# XMOS_TSBOARD_DAC.net
KiCad netlist of a schematic drawn in Altium Designer
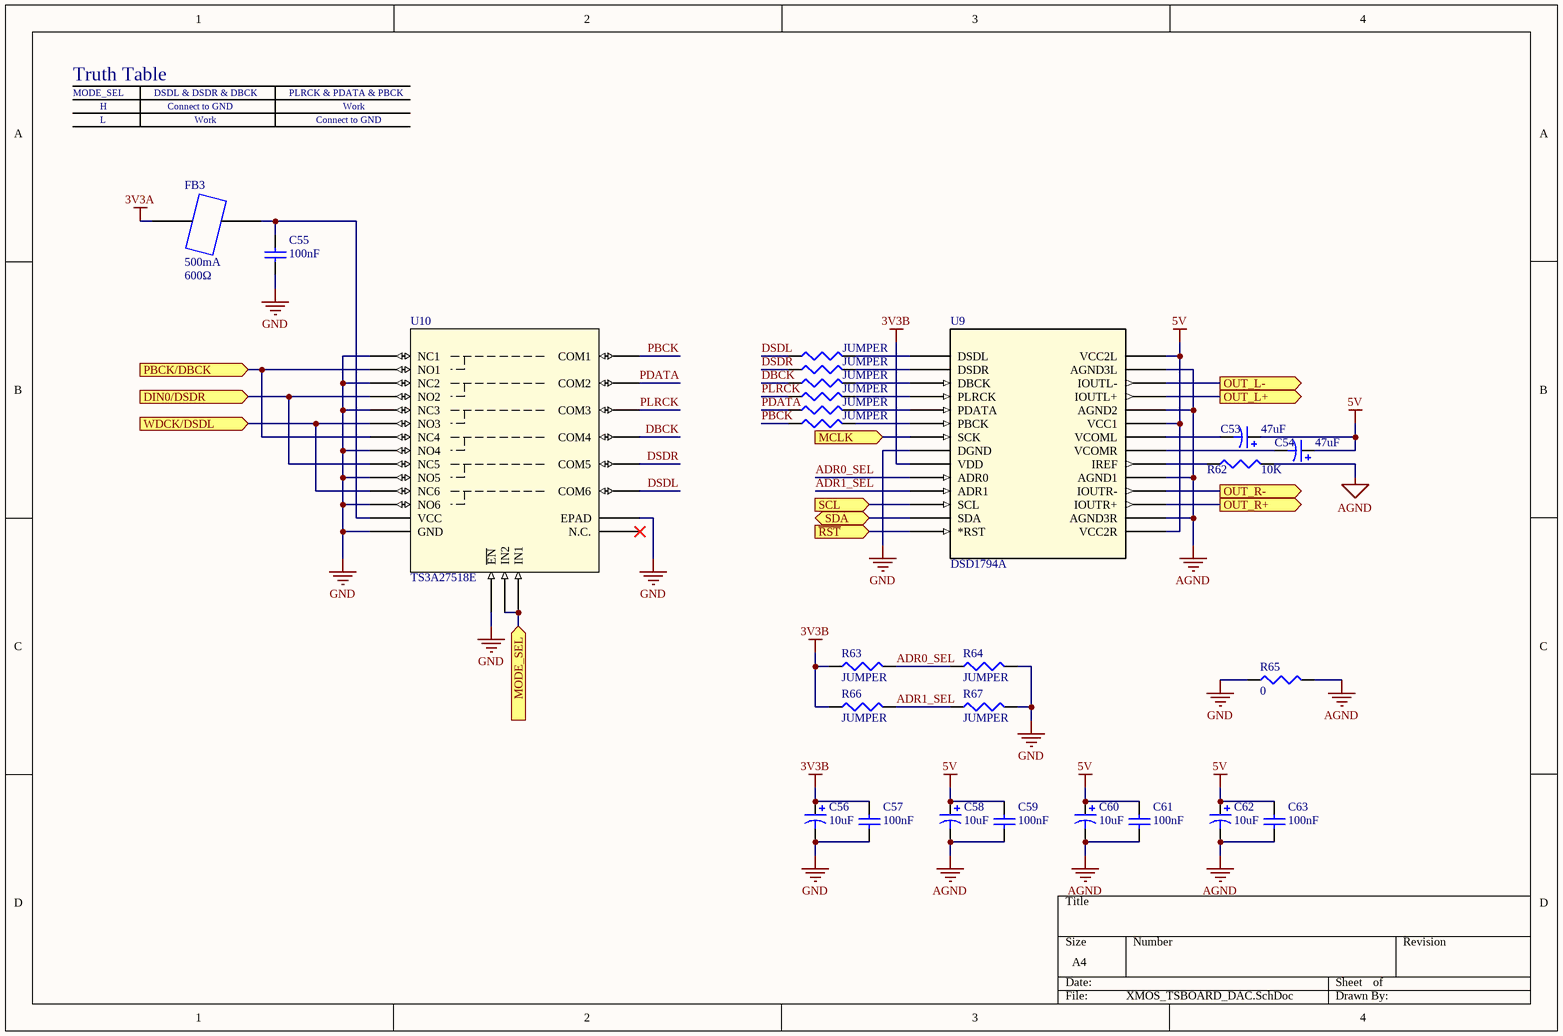
[diagram p0: XMOS_TSBOARD_DAC.SchDoc]

(export (version "E")
  (design (tool "Eeschema 10.0.6"))
  (components
    (comp (ref "C53")
      (value "47uF")
      (footprint "C0805")
      (description "Polarized Capacitor (Surface Mount)")
      (fields (field (name "Comment") "Cap Pol3") (field (name "PUBLISHER") "Altium Limited"))
      (libsource (lib "Miscellaneous Devices") (part "Cap Pol3"))
    )
    (comp (ref "C54")
      (value "47uF")
      (footprint "C0805")
      (description "Polarized Capacitor (Surface Mount)")
      (fields (field (name "Comment") "Cap Pol3") (field (name "PUBLISHER") "Altium Limited"))
      (libsource (lib "Miscellaneous Devices") (part "Cap Pol3"))
    )
    (comp (ref "C55")
      (value "100nF")
      (footprint "1608[0603]")
      (description "Capacitor (Semiconductor SIM Model)")
      (fields (field (name "Comment") "Cap Semi") (field (name "PUBLISHER") "Altium Limited"))
      (libsource (lib "Miscellaneous Devices") (part "Cap Semi"))
    )
    (comp (ref "C56")
      (value "10uF")
      (footprint "C0805")
      (description "Polarized Capacitor (Surface Mount)")
      (fields (field (name "Comment") "Cap Pol3") (field (name "PUBLISHER") "Altium Limited"))
      (libsource (lib "Miscellaneous Devices") (part "Cap Pol3"))
    )
    (comp (ref "C57")
      (value "100nF")
      (footprint "1608[0603]")
      (description "Capacitor (Semiconductor SIM Model)")
      (fields (field (name "Comment") "Cap Semi") (field (name "PUBLISHER") "Altium Limited"))
      (libsource (lib "Miscellaneous Devices") (part "Cap Semi"))
    )
    (comp (ref "C58")
      (value "10uF")
      (footprint "C0805")
      (description "Polarized Capacitor (Surface Mount)")
      (fields (field (name "Comment") "Cap Pol3") (field (name "PUBLISHER") "Altium Limited"))
      (libsource (lib "Miscellaneous Devices") (part "Cap Pol3"))
    )
    (comp (ref "C59")
      (value "100nF")
      (footprint "1608[0603]")
      (description "Capacitor (Semiconductor SIM Model)")
      (fields (field (name "Comment") "Cap Semi") (field (name "PUBLISHER") "Altium Limited"))
      (libsource (lib "Miscellaneous Devices") (part "Cap Semi"))
    )
    (comp (ref "C60")
      (value "10uF")
      (footprint "C0805")
      (description "Polarized Capacitor (Surface Mount)")
      (fields (field (name "Comment") "Cap Pol3") (field (name "PUBLISHER") "Altium Limited"))
      (libsource (lib "Miscellaneous Devices") (part "Cap Pol3"))
    )
    (comp (ref "C61")
      (value "100nF")
      (footprint "1608[0603]")
      (description "Capacitor (Semiconductor SIM Model)")
      (fields (field (name "Comment") "Cap Semi") (field (name "PUBLISHER") "Altium Limited"))
      (libsource (lib "Miscellaneous Devices") (part "Cap Semi"))
    )
    (comp (ref "C62")
      (value "10uF")
      (footprint "C0805")
      (description "Polarized Capacitor (Surface Mount)")
      (fields (field (name "Comment") "Cap Pol3") (field (name "PUBLISHER") "Altium Limited"))
      (libsource (lib "Miscellaneous Devices") (part "Cap Pol3"))
    )
    (comp (ref "C63")
      (value "100nF")
      (footprint "1608[0603]")
      (description "Capacitor (Semiconductor SIM Model)")
      (fields (field (name "Comment") "Cap Semi") (field (name "PUBLISHER") "Altium Limited"))
      (libsource (lib "Miscellaneous Devices") (part "Cap Semi"))
    )
    (comp (ref "FB3")
      (value "FerriteBeads")
      (footprint "0603")
      (description "Chip Ferrite Beads")
      (fields (field (name "RATEDCURRENT") "500mA") (field (name "IMPEDANCE(100MHZ)") "600Ω"))
      (libsource (lib "Troposphere_lib") (part "FerriteBeads"))
    )
    (comp (ref "R56")
      (value "JUMPER")
      (footprint "J1-0603")
      (description "Resistor")
      (fields (field (name "PUBLISHER") "Altium Limited"))
      (libsource (lib "Miscellaneous Devices") (part "Res3"))
    )
    (comp (ref "R57")
      (value "JUMPER")
      (footprint "J1-0603")
      (description "Resistor")
      (fields (field (name "PUBLISHER") "Altium Limited"))
      (libsource (lib "Miscellaneous Devices") (part "Res3"))
    )
    (comp (ref "R58")
      (value "JUMPER")
      (footprint "J1-0603")
      (description "Resistor")
      (fields (field (name "PUBLISHER") "Altium Limited"))
      (libsource (lib "Miscellaneous Devices") (part "Res3"))
    )
    (comp (ref "R59")
      (value "JUMPER")
      (footprint "J1-0603")
      (description "Resistor")
      (fields (field (name "PUBLISHER") "Altium Limited"))
      (libsource (lib "Miscellaneous Devices") (part "Res3"))
    )
    (comp (ref "R60")
      (value "JUMPER")
      (footprint "J1-0603")
      (description "Resistor")
      (fields (field (name "PUBLISHER") "Altium Limited"))
      (libsource (lib "Miscellaneous Devices") (part "Res3"))
    )
    (comp (ref "R61")
      (value "JUMPER")
      (footprint "J1-0603")
      (description "Resistor")
      (fields (field (name "PUBLISHER") "Altium Limited"))
      (libsource (lib "Miscellaneous Devices") (part "Res3"))
    )
    (comp (ref "R62")
      (value "10K")
      (footprint "J1-0603")
      (description "Resistor")
      (fields (field (name "Comment") "Res3") (field (name "PUBLISHER") "Altium Limited"))
      (libsource (lib "Miscellaneous Devices") (part "Res3"))
    )
    (comp (ref "R63")
      (value "JUMPER")
      (footprint "J1-0603")
      (description "Resistor")
      (fields (field (name "PUBLISHER") "Altium Limited"))
      (libsource (lib "Miscellaneous Devices") (part "Res3"))
    )
    (comp (ref "R64")
      (value "JUMPER")
      (footprint "J1-0603")
      (description "Resistor")
      (fields (field (name "PUBLISHER") "Altium Limited"))
      (libsource (lib "Miscellaneous Devices") (part "Res3"))
    )
    (comp (ref "R65")
      (value "0")
      (footprint "J1-0603")
      (description "Resistor")
      (fields (field (name "Comment") "Res3") (field (name "PUBLISHER") "Altium Limited"))
      (libsource (lib "Miscellaneous Devices") (part "Res3"))
    )
    (comp (ref "R66")
      (value "JUMPER")
      (footprint "J1-0603")
      (description "Resistor")
      (fields (field (name "PUBLISHER") "Altium Limited"))
      (libsource (lib "Miscellaneous Devices") (part "Res3"))
    )
    (comp (ref "R67")
      (value "JUMPER")
      (footprint "J1-0603")
      (description "Resistor")
      (fields (field (name "PUBLISHER") "Altium Limited"))
      (libsource (lib "Miscellaneous Devices") (part "Res3"))
    )
    (comp (ref "U9")
      (value "DSD1794A")
      (footprint "DB28")
      (description "24-Bit 192-kHz Sampling Advanced Segment Audio Stereo DAC")
      (libsource (lib "Troposphere_lib") (part "DSD1794A"))
    )
    (comp (ref "U10")
      (value "TS3A27518E")
      (footprint "RTW24")
      (description "6-Channel, 1:2 Multiplexer/Demultiplexer")
      (libsource (lib "Troposphere_lib") (part "TS3A27518E"))
    )
  )
  (nets
    (net (code "1") (name "/ADR0_SEL") (class "Default")
      (node (ref "R63") (pin "2") (pinfunction "2_2") (pintype "passive"))
      (node (ref "R64") (pin "1") (pinfunction "1_1") (pintype "passive"))
      (node (ref "U9") (pin "10") (pinfunction "ADR0_10") (pintype "input"))
    )
    (net (code "2") (name "/ADR1_SEL") (class "Default")
      (node (ref "R66") (pin "2") (pinfunction "2_2") (pintype "passive"))
      (node (ref "R67") (pin "1") (pinfunction "1_1") (pintype "passive"))
      (node (ref "U9") (pin "11") (pinfunction "ADR1_11") (pintype "input"))
    )
    (net (code "3") (name "/DBCK") (class "Default")
      (node (ref "R58") (pin "1") (pinfunction "1_1") (pintype "passive"))
      (node (ref "U10") (pin "6") (pinfunction "COM4_6") (pintype "bidirectional"))
    )
    (net (code "4") (name "/DIN0{slash}DSDR") (class "Default")
      (node (ref "U10") (pin "10") (pinfunction "NO2_10") (pintype "bidirectional"))
      (node (ref "U10") (pin "16") (pinfunction "NC5_16") (pintype "bidirectional"))
    )
    (net (code "5") (name "/DSDL") (class "Default")
      (node (ref "R56") (pin "1") (pinfunction "1_1") (pintype "passive"))
      (node (ref "U10") (pin "9") (pinfunction "COM6_9") (pintype "bidirectional"))
    )
    (net (code "6") (name "/DSDR") (class "Default")
      (node (ref "R57") (pin "1") (pinfunction "1_1") (pintype "passive"))
      (node (ref "U10") (pin "7") (pinfunction "COM5_7") (pintype "bidirectional"))
    )
    (net (code "7") (name "/MCLK") (class "Default")
      (node (ref "U9") (pin "7") (pinfunction "SCK_7") (pintype "input"))
    )
    (net (code "8") (name "/MODE_SEL") (class "Default")
      (node (ref "U10") (pin "11") (pinfunction "IN2_11") (pintype "input"))
      (node (ref "U10") (pin "21") (pinfunction "IN1_21") (pintype "input"))
    )
    (net (code "9") (name "/OUT_L+") (class "Default")
      (node (ref "U9") (pin "25") (pinfunction "IOUTL+_25") (pintype "output"))
    )
    (net (code "10") (name "/OUT_L-") (class "Default")
      (node (ref "U9") (pin "26") (pinfunction "IOUTL-_26") (pintype "output"))
    )
    (net (code "11") (name "/OUT_R+") (class "Default")
      (node (ref "U9") (pin "17") (pinfunction "IOUTR+_17") (pintype "output"))
    )
    (net (code "12") (name "/OUT_R-") (class "Default")
      (node (ref "U9") (pin "18") (pinfunction "IOUTR-_18") (pintype "output"))
    )
    (net (code "13") (name "/PBCK") (class "Default")
      (node (ref "R61") (pin "1") (pinfunction "1_1") (pintype "passive"))
      (node (ref "U10") (pin "1") (pinfunction "COM1_1") (pintype "bidirectional"))
    )
    (net (code "14") (name "/PBCK{slash}DBCK") (class "Default")
      (node (ref "U10") (pin "18") (pinfunction "NC4_18") (pintype "bidirectional"))
      (node (ref "U10") (pin "8") (pinfunction "NO1_8") (pintype "bidirectional"))
    )
    (net (code "15") (name "/PDATA") (class "Default")
      (node (ref "R60") (pin "1") (pinfunction "1_1") (pintype "passive"))
      (node (ref "U10") (pin "3") (pinfunction "COM2_3") (pintype "bidirectional"))
    )
    (net (code "16") (name "/PLRCK") (class "Default")
      (node (ref "R59") (pin "1") (pinfunction "1_1") (pintype "passive"))
      (node (ref "U10") (pin "4") (pinfunction "COM3_4") (pintype "bidirectional"))
    )
    (net (code "17") (name "/SCL") (class "Default")
      (node (ref "U9") (pin "12") (pinfunction "SCL_12") (pintype "input"))
    )
    (net (code "18") (name "/SDA") (class "Default")
      (node (ref "U9") (pin "13") (pinfunction "SDA_13") (pintype "passive"))
    )
    (net (code "19") (name "/WDCK{slash}DSDL") (class "Default")
      (node (ref "U10") (pin "12") (pinfunction "NO3_12") (pintype "bidirectional"))
      (node (ref "U10") (pin "19") (pinfunction "NC6_19") (pintype "bidirectional"))
    )
    (net (code "20") (name "/~{RST}") (class "Default")
      (node (ref "U9") (pin "14") (pinfunction "*RST_14") (pintype "input"))
    )
    (net (code "21") (name "3V3A") (class "Default")
      (node (ref "FB3") (pin "1") (pinfunction "1_1") (pintype "power_in"))
    )
    (net (code "22") (name "3V3B") (class "Default")
      (node (ref "C56") (pin "1") (pinfunction "1_1") (pintype "passive"))
      (node (ref "C57") (pin "2") (pinfunction "2_2") (pintype "passive"))
      (node (ref "R63") (pin "1") (pinfunction "1_1") (pintype "passive"))
      (node (ref "R66") (pin "1") (pinfunction "1_1") (pintype "passive"))
      (node (ref "U9") (pin "9") (pinfunction "VDD_9") (pintype "power_in"))
    )
    (net (code "23") (name "5V") (class "Default")
      (node (ref "C53") (pin "1") (pinfunction "1_1") (pintype "passive"))
      (node (ref "C54") (pin "1") (pinfunction "1_1") (pintype "passive"))
      (node (ref "C58") (pin "1") (pinfunction "1_1") (pintype "passive"))
      (node (ref "C59") (pin "2") (pinfunction "2_2") (pintype "passive"))
      (node (ref "C60") (pin "1") (pinfunction "1_1") (pintype "passive"))
      (node (ref "C61") (pin "2") (pinfunction "2_2") (pintype "passive"))
      (node (ref "C62") (pin "1") (pinfunction "1_1") (pintype "passive"))
      (node (ref "C63") (pin "2") (pinfunction "2_2") (pintype "passive"))
      (node (ref "U9") (pin "15") (pinfunction "VCC2R_15") (pintype "power_in"))
      (node (ref "U9") (pin "23") (pinfunction "VCC1_23") (pintype "power_in"))
      (node (ref "U9") (pin "28") (pinfunction "VCC2L_28") (pintype "power_in"))
    )
    (net (code "24") (name "AGND") (class "Default")
      (node (ref "C58") (pin "2") (pinfunction "2_2") (pintype "passive"))
      (node (ref "C59") (pin "1") (pinfunction "1_1") (pintype "passive"))
      (node (ref "C60") (pin "2") (pinfunction "2_2") (pintype "passive"))
      (node (ref "C61") (pin "1") (pinfunction "1_1") (pintype "passive"))
      (node (ref "C62") (pin "2") (pinfunction "2_2") (pintype "passive"))
      (node (ref "C63") (pin "1") (pinfunction "1_1") (pintype "passive"))
      (node (ref "R62") (pin "2") (pinfunction "2_2") (pintype "passive"))
      (node (ref "R65") (pin "2") (pinfunction "2_2") (pintype "passive"))
      (node (ref "U9") (pin "16") (pinfunction "AGND3R_16") (pintype "power_in"))
      (node (ref "U9") (pin "19") (pinfunction "AGND1_19") (pintype "power_in"))
      (node (ref "U9") (pin "24") (pinfunction "AGND2_24") (pintype "power_in"))
      (node (ref "U9") (pin "27") (pinfunction "AGND3L_27") (pintype "power_in"))
    )
    (net (code "25") (name "GND") (class "Default")
      (node (ref "C55") (pin "1") (pinfunction "1_1") (pintype "passive"))
      (node (ref "C56") (pin "2") (pinfunction "2_2") (pintype "passive"))
      (node (ref "C57") (pin "1") (pinfunction "1_1") (pintype "passive"))
      (node (ref "R64") (pin "2") (pinfunction "2_2") (pintype "passive"))
      (node (ref "R65") (pin "1") (pinfunction "1_1") (pintype "passive"))
      (node (ref "R67") (pin "2") (pinfunction "2_2") (pintype "passive"))
      (node (ref "U10") (pin "13") (pinfunction "NO6_13") (pintype "bidirectional"))
      (node (ref "U10") (pin "14") (pinfunction "NO4_14") (pintype "bidirectional"))
      (node (ref "U10") (pin "15") (pinfunction "NO5_15") (pintype "bidirectional"))
      (node (ref "U10") (pin "17") (pinfunction "~{EN}_17") (pintype "input"))
      (node (ref "U10") (pin "2") (pinfunction "GND_2") (pintype "power_in"))
      (node (ref "U10") (pin "20") (pinfunction "NC3_20") (pintype "bidirectional"))
      (node (ref "U10") (pin "22") (pinfunction "NC2_22") (pintype "bidirectional"))
      (node (ref "U10") (pin "23") (pinfunction "NC1_23") (pintype "bidirectional"))
      (node (ref "U10") (pin "25") (pinfunction "EPAD_25") (pintype "passive"))
      (node (ref "U9") (pin "8") (pinfunction "DGND_8") (pintype "power_in"))
    )
    (net (code "26") (name "Net-(U9-DBCK)") (class "Default")
      (node (ref "R58") (pin "2") (pinfunction "2_2") (pintype "passive"))
      (node (ref "U9") (pin "3") (pinfunction "DBCK_3") (pintype "input"))
    )
    (net (code "27") (name "Net-(U9-DSDL)") (class "Default")
      (node (ref "R56") (pin "2") (pinfunction "2_2") (pintype "passive"))
      (node (ref "U9") (pin "1") (pinfunction "DSDL_1") (pintype "passive"))
    )
    (net (code "28") (name "Net-(U9-DSDR)") (class "Default")
      (node (ref "R57") (pin "2") (pinfunction "2_2") (pintype "passive"))
      (node (ref "U9") (pin "2") (pinfunction "DSDR_2") (pintype "passive"))
    )
    (net (code "29") (name "Net-(U9-IREF)") (class "Default")
      (node (ref "R62") (pin "1") (pinfunction "1_1") (pintype "passive"))
      (node (ref "U9") (pin "20") (pinfunction "IREF_20") (pintype "output"))
    )
    (net (code "30") (name "Net-(U9-PBCK)") (class "Default")
      (node (ref "R61") (pin "2") (pinfunction "2_2") (pintype "passive"))
      (node (ref "U9") (pin "6") (pinfunction "PBCK_6") (pintype "input"))
    )
    (net (code "31") (name "Net-(U9-PDATA)") (class "Default")
      (node (ref "R60") (pin "2") (pinfunction "2_2") (pintype "passive"))
      (node (ref "U9") (pin "5") (pinfunction "PDATA_5") (pintype "input"))
    )
    (net (code "32") (name "Net-(U9-PLRCK)") (class "Default")
      (node (ref "R59") (pin "2") (pinfunction "2_2") (pintype "passive"))
      (node (ref "U9") (pin "4") (pinfunction "PLRCK_4") (pintype "input"))
    )
    (net (code "33") (name "Net-(U9-VCOML)") (class "Default")
      (node (ref "C53") (pin "2") (pinfunction "2_2") (pintype "passive"))
      (node (ref "U9") (pin "22") (pinfunction "VCOML_22") (pintype "power_in"))
    )
    (net (code "34") (name "Net-(U9-VCOMR)") (class "Default")
      (node (ref "C54") (pin "2") (pinfunction "2_2") (pintype "passive"))
      (node (ref "U9") (pin "21") (pinfunction "VCOMR_21") (pintype "power_in"))
    )
    (net (code "35") (name "Net-(U10-VCC)") (class "Default")
      (node (ref "C55") (pin "2") (pinfunction "2_2") (pintype "passive"))
      (node (ref "FB3") (pin "2") (pinfunction "2_2") (pintype "power_in"))
      (node (ref "U10") (pin "5") (pinfunction "VCC_5") (pintype "power_in"))
    )
    (net (code "36") (name "unconnected-(U10-N.C.-Pad24)") (class "Default")
      (node (ref "U10") (pin "24") (pinfunction "N.C._24") (pintype "passive+no_connect"))
    )
  )
)
